# mainboard.net
KiCad netlist of a schematic drawn in EAGLE
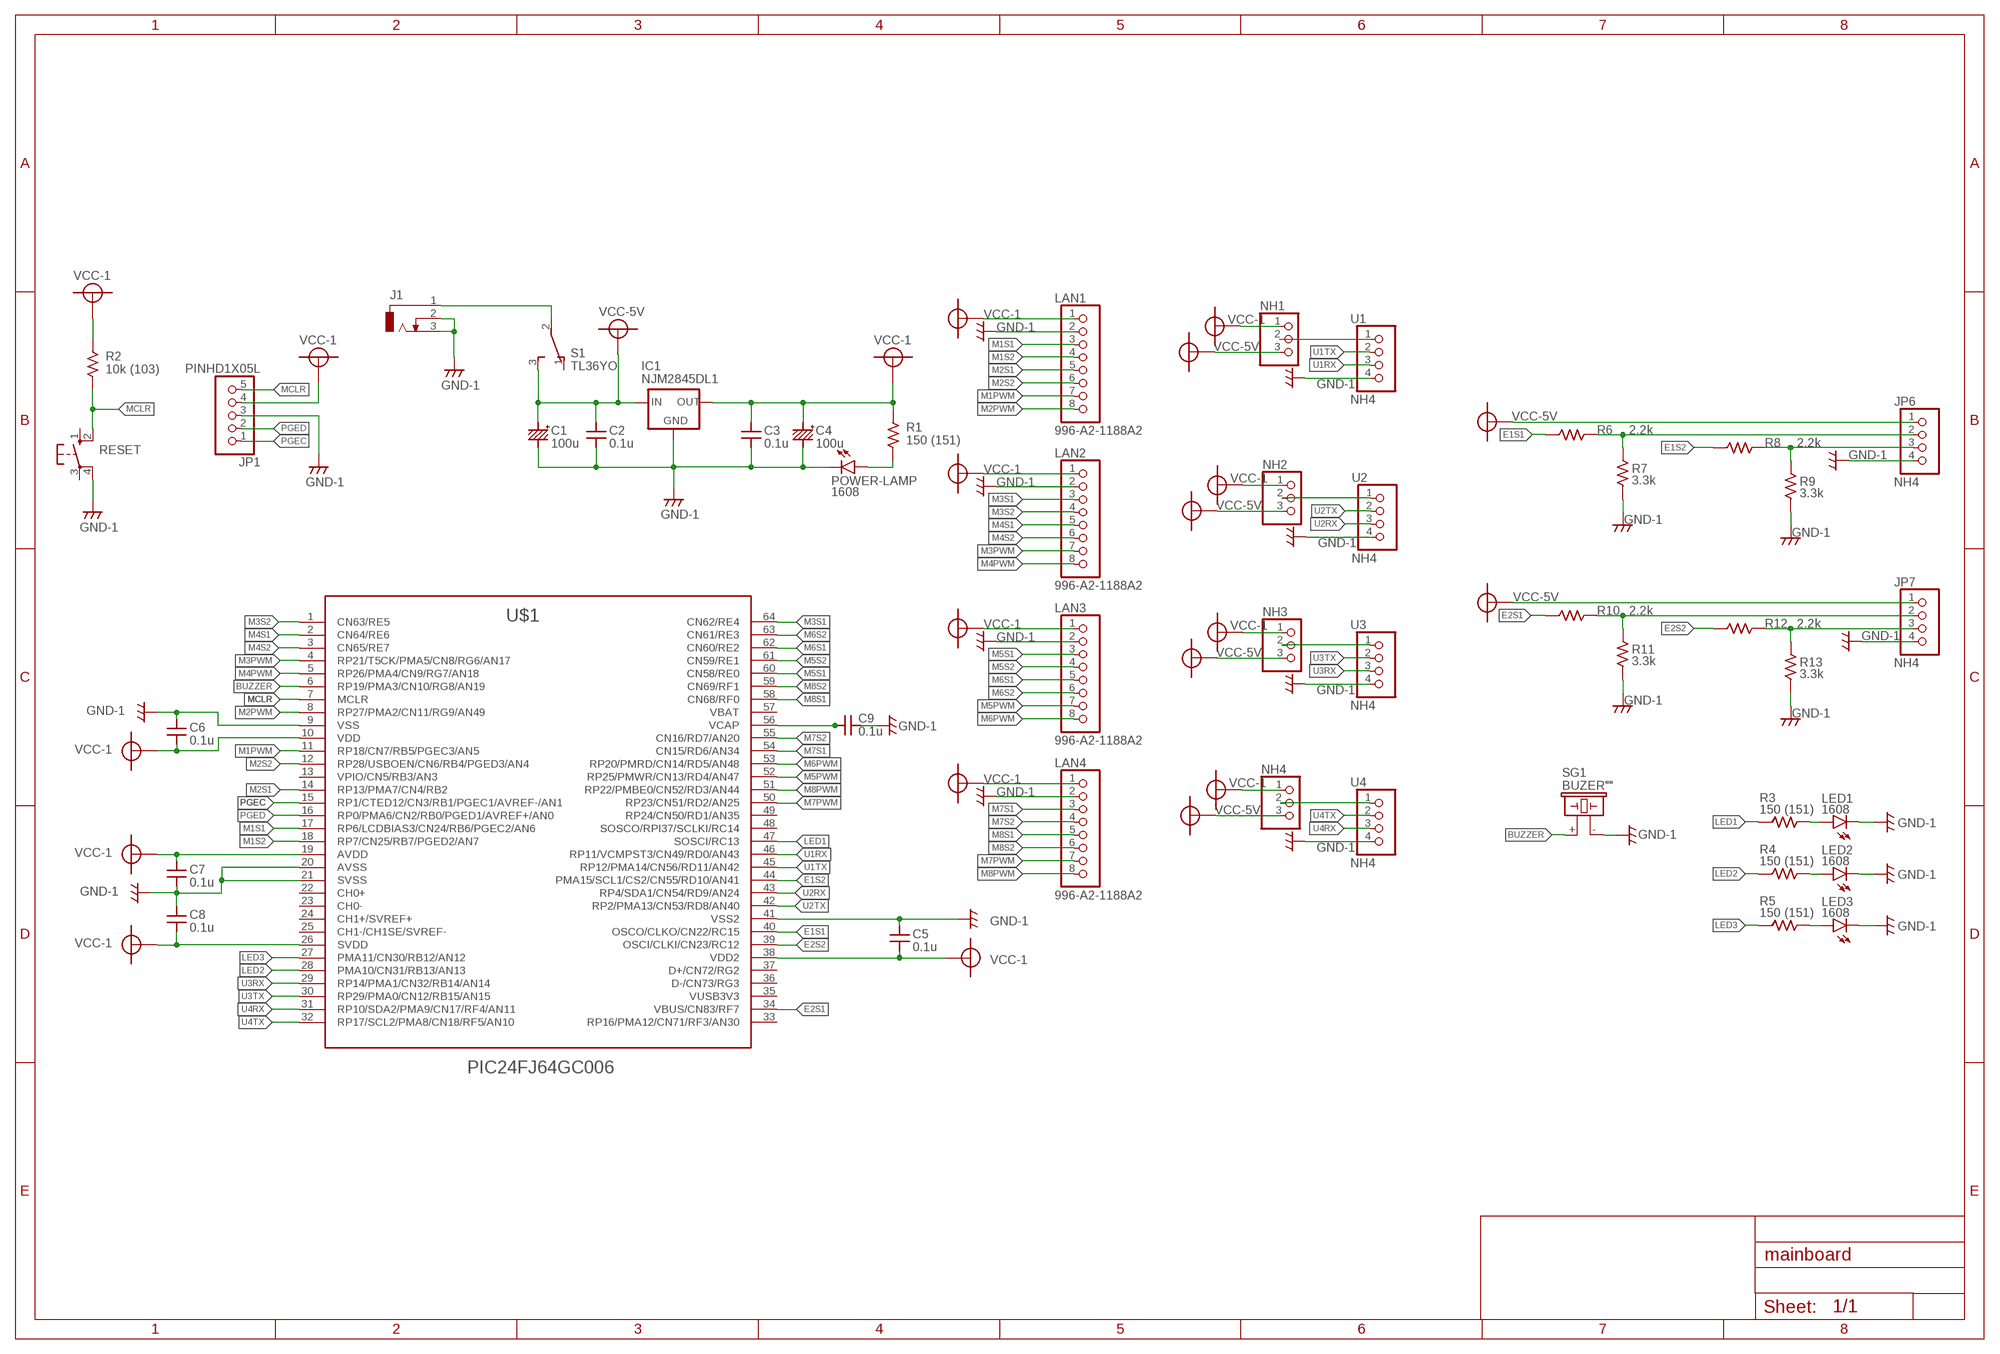
[diagram p0: schematic, sheet 1]

(export (version "E")
  (design (tool "Eeschema 10.0.6"))
  (components
    (comp (ref "C1")
      (value "100u")
      (footprint "eagle-import:CC_3")
      (libsource (lib "eagle-import") (part "C+25V100"))
    )
    (comp (ref "C2")
      (value "0.1u")
      (footprint "eagle-import:C1608")
      (libsource (lib "eagle-import") (part "CC1068"))
    )
    (comp (ref "C3")
      (value "0.1u")
      (footprint "eagle-import:C1608")
      (libsource (lib "eagle-import") (part "CC1068"))
    )
    (comp (ref "C4")
      (value "100u")
      (footprint "eagle-import:CC_3")
      (libsource (lib "eagle-import") (part "C+25V100"))
    )
    (comp (ref "C5")
      (value "0.1u")
      (footprint "eagle-import:C1608")
      (libsource (lib "eagle-import") (part "CC1068"))
    )
    (comp (ref "C6")
      (value "0.1u")
      (footprint "eagle-import:C1608")
      (libsource (lib "eagle-import") (part "CC1068"))
    )
    (comp (ref "C7")
      (value "0.1u")
      (footprint "eagle-import:C1608")
      (libsource (lib "eagle-import") (part "CC1068"))
    )
    (comp (ref "C8")
      (value "0.1u")
      (footprint "eagle-import:C1608")
      (libsource (lib "eagle-import") (part "CC1068"))
    )
    (comp (ref "C9")
      (value "0.1u")
      (footprint "eagle-import:C1608")
      (libsource (lib "eagle-import") (part "CC1068"))
    )
    (comp (ref "IC1")
      (value "NJM2845DL1")
      (footprint "eagle-import:TO252")
      (libsource (lib "eagle-import") (part "NJM2845DL1"))
    )
    (comp (ref "J1")
      (value "DCJ0303")
      (footprint "eagle-import:DCJ0303")
      (libsource (lib "eagle-import") (part "DCJ0303"))
    )
    (comp (ref "JP1")
      (value "PINHD1X05L")
      (footprint "eagle-import:1X05L")
      (libsource (lib "eagle-import") (part "PINHD1X05L"))
    )
    (comp (ref "JP6")
      (value "NH4")
      (footprint "eagle-import:NH4")
      (libsource (lib "eagle-import") (part "NH4"))
    )
    (comp (ref "JP7")
      (value "NH4")
      (footprint "eagle-import:NH4")
      (libsource (lib "eagle-import") (part "NH4"))
    )
    (comp (ref "LAN1")
      (value "996-A2-1188A2")
      (footprint "eagle-import:996-A2-1188A2")
      (libsource (lib "eagle-import") (part "996-A2-1188A2"))
    )
    (comp (ref "LAN2")
      (value "996-A2-1188A2")
      (footprint "eagle-import:996-A2-1188A2")
      (libsource (lib "eagle-import") (part "996-A2-1188A2"))
    )
    (comp (ref "LAN3")
      (value "996-A2-1188A2")
      (footprint "eagle-import:996-A2-1188A2")
      (libsource (lib "eagle-import") (part "996-A2-1188A2"))
    )
    (comp (ref "LAN4")
      (value "996-A2-1188A2")
      (footprint "eagle-import:996-A2-1188A2")
      (libsource (lib "eagle-import") (part "996-A2-1188A2"))
    )
    (comp (ref "LED1")
      (value "1608")
      (footprint "eagle-import:CHIP-LED0603")
      (libsource (lib "eagle-import") (part "LEDCHIP-LED0603"))
    )
    (comp (ref "LED2")
      (value "1608")
      (footprint "eagle-import:CHIP-LED0603")
      (libsource (lib "eagle-import") (part "LEDCHIP-LED0603"))
    )
    (comp (ref "LED3")
      (value "1608")
      (footprint "eagle-import:CHIP-LED0603")
      (libsource (lib "eagle-import") (part "LEDCHIP-LED0603"))
    )
    (comp (ref "NH1")
      (value "PINHD-1X3")
      (footprint "eagle-import:1X03")
      (libsource (lib "eagle-import") (part "PINHD-1X3"))
    )
    (comp (ref "NH2")
      (value "PINHD-1X3")
      (footprint "eagle-import:1X03")
      (libsource (lib "eagle-import") (part "PINHD-1X3"))
    )
    (comp (ref "NH3")
      (value "PINHD-1X3")
      (footprint "eagle-import:1X03")
      (libsource (lib "eagle-import") (part "PINHD-1X3"))
    )
    (comp (ref "NH4")
      (value "PINHD-1X3")
      (footprint "eagle-import:1X03")
      (libsource (lib "eagle-import") (part "PINHD-1X3"))
    )
    (comp (ref "POWER-LAMP")
      (value "1608")
      (footprint "eagle-import:CHIP-LED0603")
      (libsource (lib "eagle-import") (part "LEDCHIP-LED0603"))
    )
    (comp (ref "R1")
      (value "150 (151)")
      (footprint "eagle-import:C1608")
      (libsource (lib "eagle-import") (part "R1/10W"))
    )
    (comp (ref "R2")
      (value "10k (103)")
      (footprint "eagle-import:C1608")
      (libsource (lib "eagle-import") (part "R1/10W"))
    )
    (comp (ref "R3")
      (value "150 (151)")
      (footprint "eagle-import:C1608")
      (libsource (lib "eagle-import") (part "R1/10W"))
    )
    (comp (ref "R4")
      (value "150 (151)")
      (footprint "eagle-import:C1608")
      (libsource (lib "eagle-import") (part "R1/10W"))
    )
    (comp (ref "R5")
      (value "150 (151)")
      (footprint "eagle-import:C1608")
      (libsource (lib "eagle-import") (part "R1/10W"))
    )
    (comp (ref "R6")
      (value "2.2k")
      (footprint "eagle-import:C1608")
      (libsource (lib "eagle-import") (part "R1/10W"))
    )
    (comp (ref "R7")
      (value "3.3k")
      (footprint "eagle-import:C1608")
      (libsource (lib "eagle-import") (part "R1/10W"))
    )
    (comp (ref "R8")
      (value "2.2k")
      (footprint "eagle-import:C1608")
      (libsource (lib "eagle-import") (part "R1/10W"))
    )
    (comp (ref "R9")
      (value "3.3k")
      (footprint "eagle-import:C1608")
      (libsource (lib "eagle-import") (part "R1/10W"))
    )
    (comp (ref "R10")
      (value "2.2k")
      (footprint "eagle-import:C1608")
      (libsource (lib "eagle-import") (part "R1/10W"))
    )
    (comp (ref "R11")
      (value "3.3k")
      (footprint "eagle-import:C1608")
      (libsource (lib "eagle-import") (part "R1/10W"))
    )
    (comp (ref "R12")
      (value "2.2k")
      (footprint "eagle-import:C1608")
      (libsource (lib "eagle-import") (part "R1/10W"))
    )
    (comp (ref "R13")
      (value "3.3k")
      (footprint "eagle-import:C1608")
      (libsource (lib "eagle-import") (part "R1/10W"))
    )
    (comp (ref "RESET")
      (value "10-XX")
      (footprint "eagle-import:B3F-10XX")
      (fields (field (name "MPN") "B3F-1000"))
      (libsource (lib "eagle-import") (part "10-XX"))
    )
    (comp (ref "S1")
      (value "TL36YO")
      (footprint "eagle-import:TL3XYO")
      (libsource (lib "eagle-import") (part "TL36YO"))
    )
    (comp (ref "SG1")
      (value "BUZER\"\"")
      (footprint "eagle-import:F_CM12P")
      (libsource (lib "eagle-import") (part "BUZER{dblquote}{dblquote}"))
    )
    (comp (ref "U$1")
      (value "PIC24FJ64GC006")
      (footprint "eagle-import:TQFP64-10X10")
      (libsource (lib "eagle-import") (part "PIC24FJ64GC006"))
    )
    (comp (ref "U1")
      (value "NH4")
      (footprint "eagle-import:NH4")
      (libsource (lib "eagle-import") (part "NH4"))
    )
    (comp (ref "U2")
      (value "NH4")
      (footprint "eagle-import:NH4")
      (libsource (lib "eagle-import") (part "NH4"))
    )
    (comp (ref "U3")
      (value "NH4")
      (footprint "eagle-import:NH4")
      (libsource (lib "eagle-import") (part "NH4"))
    )
    (comp (ref "U4")
      (value "NH4")
      (footprint "eagle-import:NH4")
      (libsource (lib "eagle-import") (part "NH4"))
    )
  )
  (nets
    (net (code "1") (name "BUZZER") (class "Default")
      (node (ref "SG1") (pin "+") (pinfunction "1_+") (pintype "passive"))
      (node (ref "U$1") (pin "6") (pinfunction "RP19/PMA3/CN10/RG8/AN19_6") (pintype "bidirectional"))
    )
    (net (code "2") (name "E1S1") (class "Default")
      (node (ref "R6") (pin "2") (pinfunction "P$2_2") (pintype "passive"))
      (node (ref "U$1") (pin "40") (pinfunction "OSCO/CLKO/CN22/RC15_40") (pintype "bidirectional"))
    )
    (net (code "3") (name "E1S2") (class "Default")
      (node (ref "R8") (pin "2") (pinfunction "P$2_2") (pintype "passive"))
      (node (ref "U$1") (pin "44") (pinfunction "PMA15/SCL1/CS2/CN55/RD10/AN41_44") (pintype "bidirectional"))
    )
    (net (code "4") (name "E2S1") (class "Default")
      (node (ref "R10") (pin "2") (pinfunction "P$2_2") (pintype "passive"))
      (node (ref "U$1") (pin "34") (pinfunction "VBUS/CN83/RF7_34") (pintype "bidirectional"))
    )
    (net (code "5") (name "E2S2") (class "Default")
      (node (ref "R12") (pin "2") (pinfunction "P$2_2") (pintype "passive"))
      (node (ref "U$1") (pin "39") (pinfunction "OSCI/CLKI/CN23/RC12_39") (pintype "bidirectional"))
    )
    (net (code "6") (name "GND-1") (class "Default")
      (node (ref "C1") (pin "-") (pinfunction "P$2-_-") (pintype "passive"))
      (node (ref "C2") (pin "2") (pinfunction "P$2_2") (pintype "passive"))
      (node (ref "C3") (pin "2") (pinfunction "P$2_2") (pintype "passive"))
      (node (ref "C4") (pin "-") (pinfunction "P$2-_-") (pintype "passive"))
      (node (ref "C5") (pin "1") (pinfunction "P$1_1") (pintype "passive"))
      (node (ref "C6") (pin "1") (pinfunction "P$1_1") (pintype "passive"))
      (node (ref "C7") (pin "2") (pinfunction "P$2_2") (pintype "passive"))
      (node (ref "C8") (pin "1") (pinfunction "P$1_1") (pintype "passive"))
      (node (ref "C9") (pin "2") (pinfunction "P$2_2") (pintype "passive"))
      (node (ref "IC1") (pin "2") (pinfunction "GND_2") (pintype "input"))
      (node (ref "J1") (pin "2") (pinfunction "2_2") (pintype "passive"))
      (node (ref "J1") (pin "3") (pinfunction "3_3") (pintype "passive"))
      (node (ref "JP1") (pin "3") (pinfunction "P$3_3") (pintype "bidirectional"))
      (node (ref "JP6") (pin "4") (pinfunction "P$4_4") (pintype "bidirectional"))
      (node (ref "JP7") (pin "4") (pinfunction "P$4_4") (pintype "bidirectional"))
      (node (ref "LAN1") (pin "2") (pinfunction "P$2_2") (pintype "bidirectional"))
      (node (ref "LAN2") (pin "2") (pinfunction "P$2_2") (pintype "bidirectional"))
      (node (ref "LAN3") (pin "2") (pinfunction "P$2_2") (pintype "bidirectional"))
      (node (ref "LAN4") (pin "2") (pinfunction "P$2_2") (pintype "bidirectional"))
      (node (ref "LED1") (pin "C") (pinfunction "C_C") (pintype "passive"))
      (node (ref "LED2") (pin "C") (pinfunction "C_C") (pintype "passive"))
      (node (ref "LED3") (pin "C") (pinfunction "C_C") (pintype "passive"))
      (node (ref "POWER-LAMP") (pin "C") (pinfunction "C_C") (pintype "passive"))
      (node (ref "R11") (pin "2") (pinfunction "P$2_2") (pintype "passive"))
      (node (ref "R13") (pin "2") (pinfunction "P$2_2") (pintype "passive"))
      (node (ref "R7") (pin "2") (pinfunction "P$2_2") (pintype "passive"))
      (node (ref "R9") (pin "2") (pinfunction "P$2_2") (pintype "passive"))
      (node (ref "RESET") (pin "4") (pinfunction "P1_4") (pintype "passive"))
      (node (ref "SG1") (pin "-") (pinfunction "2_-") (pintype "passive"))
      (node (ref "U$1") (pin "20") (pinfunction "AVSS_20") (pintype "bidirectional"))
      (node (ref "U$1") (pin "21") (pinfunction "SVSS_21") (pintype "bidirectional"))
      (node (ref "U$1") (pin "41") (pinfunction "VSS2_41") (pintype "bidirectional"))
      (node (ref "U$1") (pin "9") (pinfunction "VSS_9") (pintype "bidirectional"))
      (node (ref "U1") (pin "4") (pinfunction "P$4_4") (pintype "bidirectional"))
      (node (ref "U2") (pin "4") (pinfunction "P$4_4") (pintype "bidirectional"))
      (node (ref "U3") (pin "4") (pinfunction "P$4_4") (pintype "bidirectional"))
      (node (ref "U4") (pin "4") (pinfunction "P$4_4") (pintype "bidirectional"))
    )
    (net (code "7") (name "LED1") (class "Default")
      (node (ref "R3") (pin "2") (pinfunction "P$2_2") (pintype "passive"))
      (node (ref "U$1") (pin "47") (pinfunction "SOSCI/RC13_47") (pintype "bidirectional"))
    )
    (net (code "8") (name "LED2") (class "Default")
      (node (ref "R4") (pin "2") (pinfunction "P$2_2") (pintype "passive"))
      (node (ref "U$1") (pin "28") (pinfunction "PMA10/CN31/RB13/AN13_28") (pintype "bidirectional"))
    )
    (net (code "9") (name "LED3") (class "Default")
      (node (ref "R5") (pin "2") (pinfunction "P$2_2") (pintype "passive"))
      (node (ref "U$1") (pin "27") (pinfunction "PMA11/CN30/RB12/AN12_27") (pintype "bidirectional"))
    )
    (net (code "10") (name "M1PWM") (class "Default")
      (node (ref "LAN1") (pin "7") (pinfunction "P$7_7") (pintype "bidirectional"))
      (node (ref "U$1") (pin "11") (pinfunction "RP18/CN7/RB5/PGEC3/AN5_11") (pintype "bidirectional"))
    )
    (net (code "11") (name "M1S1") (class "Default")
      (node (ref "LAN1") (pin "3") (pinfunction "P$3_3") (pintype "bidirectional"))
      (node (ref "U$1") (pin "17") (pinfunction "RP6/LCDBIAS3/CN24/RB6/PGEC2/AN6_17") (pintype "bidirectional"))
    )
    (net (code "12") (name "M1S2") (class "Default")
      (node (ref "LAN1") (pin "4") (pinfunction "P$4_4") (pintype "bidirectional"))
      (node (ref "U$1") (pin "18") (pinfunction "RP7/CN25/RB7/PGED2/AN7_18") (pintype "bidirectional"))
    )
    (net (code "13") (name "M2PWM") (class "Default")
      (node (ref "LAN1") (pin "8") (pinfunction "P$8_8") (pintype "bidirectional"))
      (node (ref "U$1") (pin "8") (pinfunction "RP27/PMA2/CN11/RG9/AN49_8") (pintype "bidirectional"))
    )
    (net (code "14") (name "M2S1") (class "Default")
      (node (ref "LAN1") (pin "5") (pinfunction "P$5_5") (pintype "bidirectional"))
      (node (ref "U$1") (pin "14") (pinfunction "RP13/PMA7/CN4/RB2_14") (pintype "bidirectional"))
    )
    (net (code "15") (name "M2S2") (class "Default")
      (node (ref "LAN1") (pin "6") (pinfunction "P$6_6") (pintype "bidirectional"))
      (node (ref "U$1") (pin "12") (pinfunction "RP28/USBOEN/CN6/RB4/PGED3/AN4_12") (pintype "bidirectional"))
    )
    (net (code "16") (name "M3PWM") (class "Default")
      (node (ref "LAN2") (pin "7") (pinfunction "P$7_7") (pintype "bidirectional"))
      (node (ref "U$1") (pin "4") (pinfunction "RP21/T5CK/PMA5/CN8/RG6/AN17_4") (pintype "bidirectional"))
    )
    (net (code "17") (name "M3S1") (class "Default")
      (node (ref "LAN2") (pin "3") (pinfunction "P$3_3") (pintype "bidirectional"))
      (node (ref "U$1") (pin "64") (pinfunction "CN62/RE4_64") (pintype "bidirectional"))
    )
    (net (code "18") (name "M3S2") (class "Default")
      (node (ref "LAN2") (pin "4") (pinfunction "P$4_4") (pintype "bidirectional"))
      (node (ref "U$1") (pin "1") (pinfunction "CN63/RE5_1") (pintype "bidirectional"))
    )
    (net (code "19") (name "M4PWM") (class "Default")
      (node (ref "LAN2") (pin "8") (pinfunction "P$8_8") (pintype "bidirectional"))
      (node (ref "U$1") (pin "5") (pinfunction "RP26/PMA4/CN9/RG7/AN18_5") (pintype "bidirectional"))
    )
    (net (code "20") (name "M4S1") (class "Default")
      (node (ref "LAN2") (pin "5") (pinfunction "P$5_5") (pintype "bidirectional"))
      (node (ref "U$1") (pin "2") (pinfunction "CN64/RE6_2") (pintype "bidirectional"))
    )
    (net (code "21") (name "M4S2") (class "Default")
      (node (ref "LAN2") (pin "6") (pinfunction "P$6_6") (pintype "bidirectional"))
      (node (ref "U$1") (pin "3") (pinfunction "CN65/RE7_3") (pintype "bidirectional"))
    )
    (net (code "22") (name "M5PWM") (class "Default")
      (node (ref "LAN3") (pin "7") (pinfunction "P$7_7") (pintype "bidirectional"))
      (node (ref "U$1") (pin "52") (pinfunction "RP25/PMWR/CN13/RD4/AN47_52") (pintype "bidirectional"))
    )
    (net (code "23") (name "M5S1") (class "Default")
      (node (ref "LAN3") (pin "3") (pinfunction "P$3_3") (pintype "bidirectional"))
      (node (ref "U$1") (pin "60") (pinfunction "CN58/RE0_60") (pintype "bidirectional"))
    )
    (net (code "24") (name "M5S2") (class "Default")
      (node (ref "LAN3") (pin "4") (pinfunction "P$4_4") (pintype "bidirectional"))
      (node (ref "U$1") (pin "61") (pinfunction "CN59/RE1_61") (pintype "bidirectional"))
    )
    (net (code "25") (name "M6PWM") (class "Default")
      (node (ref "LAN3") (pin "8") (pinfunction "P$8_8") (pintype "bidirectional"))
      (node (ref "U$1") (pin "53") (pinfunction "RP20/PMRD/CN14/RD5/AN48_53") (pintype "bidirectional"))
    )
    (net (code "26") (name "M6S1") (class "Default")
      (node (ref "LAN3") (pin "5") (pinfunction "P$5_5") (pintype "bidirectional"))
      (node (ref "U$1") (pin "62") (pinfunction "CN60/RE2_62") (pintype "bidirectional"))
    )
    (net (code "27") (name "M6S2") (class "Default")
      (node (ref "LAN3") (pin "6") (pinfunction "P$6_6") (pintype "bidirectional"))
      (node (ref "U$1") (pin "63") (pinfunction "CN61/RE3_63") (pintype "bidirectional"))
    )
    (net (code "28") (name "M7PWM") (class "Default")
      (node (ref "LAN4") (pin "7") (pinfunction "P$7_7") (pintype "bidirectional"))
      (node (ref "U$1") (pin "50") (pinfunction "RP23/CN51/RD2/AN25_50") (pintype "bidirectional"))
    )
    (net (code "29") (name "M7S1") (class "Default")
      (node (ref "LAN4") (pin "3") (pinfunction "P$3_3") (pintype "bidirectional"))
      (node (ref "U$1") (pin "54") (pinfunction "CN15/RD6/AN34_54") (pintype "bidirectional"))
    )
    (net (code "30") (name "M7S2") (class "Default")
      (node (ref "LAN4") (pin "4") (pinfunction "P$4_4") (pintype "bidirectional"))
      (node (ref "U$1") (pin "55") (pinfunction "CN16/RD7/AN20_55") (pintype "bidirectional"))
    )
    (net (code "31") (name "M8PWM") (class "Default")
      (node (ref "LAN4") (pin "8") (pinfunction "P$8_8") (pintype "bidirectional"))
      (node (ref "U$1") (pin "51") (pinfunction "RP22/PMBE0/CN52/RD3/AN44_51") (pintype "bidirectional"))
    )
    (net (code "32") (name "M8S1") (class "Default")
      (node (ref "LAN4") (pin "5") (pinfunction "P$5_5") (pintype "bidirectional"))
      (node (ref "U$1") (pin "58") (pinfunction "CN68/RF0_58") (pintype "bidirectional"))
    )
    (net (code "33") (name "M8S2") (class "Default")
      (node (ref "LAN4") (pin "6") (pinfunction "P$6_6") (pintype "bidirectional"))
      (node (ref "U$1") (pin "59") (pinfunction "CN69/RF1_59") (pintype "bidirectional"))
    )
    (net (code "34") (name "MCLR") (class "Default")
      (node (ref "JP1") (pin "5") (pinfunction "P$5_5") (pintype "bidirectional"))
      (node (ref "R2") (pin "1") (pinfunction "P$1_1") (pintype "passive"))
      (node (ref "RESET") (pin "2") (pinfunction "S1_2") (pintype "passive"))
      (node (ref "U$1") (pin "7") (pinfunction "MCLR_7") (pintype "bidirectional"))
    )
    (net (code "35") (name "Net-(C9-P$1)") (class "Default")
      (node (ref "C9") (pin "1") (pinfunction "P$1_1") (pintype "passive"))
      (node (ref "U$1") (pin "56") (pinfunction "VCAP_56") (pintype "bidirectional"))
    )
    (net (code "36") (name "Net-(JP6-P$2)") (class "Default")
      (node (ref "JP6") (pin "2") (pinfunction "P$2_2") (pintype "bidirectional"))
      (node (ref "R6") (pin "1") (pinfunction "P$1_1") (pintype "passive"))
      (node (ref "R7") (pin "1") (pinfunction "P$1_1") (pintype "passive"))
    )
    (net (code "37") (name "Net-(JP6-P$3)") (class "Default")
      (node (ref "JP6") (pin "3") (pinfunction "P$3_3") (pintype "bidirectional"))
      (node (ref "R8") (pin "1") (pinfunction "P$1_1") (pintype "passive"))
      (node (ref "R9") (pin "1") (pinfunction "P$1_1") (pintype "passive"))
    )
    (net (code "38") (name "Net-(JP7-P$2)") (class "Default")
      (node (ref "JP7") (pin "2") (pinfunction "P$2_2") (pintype "bidirectional"))
      (node (ref "R10") (pin "1") (pinfunction "P$1_1") (pintype "passive"))
      (node (ref "R11") (pin "1") (pinfunction "P$1_1") (pintype "passive"))
    )
    (net (code "39") (name "Net-(JP7-P$3)") (class "Default")
      (node (ref "JP7") (pin "3") (pinfunction "P$3_3") (pintype "bidirectional"))
      (node (ref "R12") (pin "1") (pinfunction "P$1_1") (pintype "passive"))
      (node (ref "R13") (pin "1") (pinfunction "P$1_1") (pintype "passive"))
    )
    (net (code "40") (name "Net-(R1-P$1)") (class "Default")
      (node (ref "POWER-LAMP") (pin "A") (pinfunction "A_A") (pintype "passive"))
      (node (ref "R1") (pin "1") (pinfunction "P$1_1") (pintype "passive"))
    )
    (net (code "41") (name "Net-(R3-P$1)") (class "Default")
      (node (ref "LED1") (pin "A") (pinfunction "A_A") (pintype "passive"))
      (node (ref "R3") (pin "1") (pinfunction "P$1_1") (pintype "passive"))
    )
    (net (code "42") (name "Net-(R4-P$1)") (class "Default")
      (node (ref "LED2") (pin "A") (pinfunction "A_A") (pintype "passive"))
      (node (ref "R4") (pin "1") (pinfunction "P$1_1") (pintype "passive"))
    )
    (net (code "43") (name "Net-(R5-P$1)") (class "Default")
      (node (ref "LED3") (pin "A") (pinfunction "A_A") (pintype "passive"))
      (node (ref "R5") (pin "1") (pinfunction "P$1_1") (pintype "passive"))
    )
    (net (code "44") (name "Net-(S1-P)") (class "Default")
      (node (ref "J1") (pin "1") (pinfunction "1_1") (pintype "passive"))
      (node (ref "S1") (pin "2") (pinfunction "P_2") (pintype "passive"))
    )
    (net (code "45") (name "Net-(U1-P$1)") (class "Default")
      (node (ref "NH1") (pin "2") (pinfunction "2_2") (pintype "passive"))
      (node (ref "U1") (pin "1") (pinfunction "P$1_1") (pintype "bidirectional"))
    )
    (net (code "46") (name "Net-(U2-P$1)") (class "Default")
      (node (ref "NH2") (pin "2") (pinfunction "2_2") (pintype "passive"))
      (node (ref "U2") (pin "1") (pinfunction "P$1_1") (pintype "bidirectional"))
    )
    (net (code "47") (name "Net-(U3-P$1)") (class "Default")
      (node (ref "NH3") (pin "2") (pinfunction "2_2") (pintype "passive"))
      (node (ref "U3") (pin "1") (pinfunction "P$1_1") (pintype "bidirectional"))
    )
    (net (code "48") (name "Net-(U4-P$1)") (class "Default")
      (node (ref "NH4") (pin "2") (pinfunction "2_2") (pintype "passive"))
      (node (ref "U4") (pin "1") (pinfunction "P$1_1") (pintype "bidirectional"))
    )
    (net (code "49") (name "PGEC") (class "Default")
      (node (ref "JP1") (pin "1") (pinfunction "P$1_1") (pintype "bidirectional"))
      (node (ref "U$1") (pin "15") (pinfunction "RP1/CTED12/CN3/RB1/PGEC1/AVREF-/AN1_15") (pintype "bidirectional"))
    )
    (net (code "50") (name "PGED") (class "Default")
      (node (ref "JP1") (pin "2") (pinfunction "P$2_2") (pintype "bidirectional"))
      (node (ref "U$1") (pin "16") (pinfunction "RP0/PMA6/CN2/RB0/PGED1/AVREF+/AN0_16") (pintype "bidirectional"))
    )
    (net (code "51") (name "U1RX") (class "Default")
      (node (ref "U$1") (pin "46") (pinfunction "RP11/VCMPST3/CN49/RD0/AN43_46") (pintype "bidirectional"))
      (node (ref "U1") (pin "3") (pinfunction "P$3_3") (pintype "bidirectional"))
    )
    (net (code "52") (name "U1TX") (class "Default")
      (node (ref "U$1") (pin "45") (pinfunction "RP12/PMA14/CN56/RD11/AN42_45") (pintype "bidirectional"))
      (node (ref "U1") (pin "2") (pinfunction "P$2_2") (pintype "bidirectional"))
    )
    (net (code "53") (name "U2RX") (class "Default")
      (node (ref "U$1") (pin "43") (pinfunction "RP4/SDA1/CN54/RD9/AN24_43") (pintype "bidirectional"))
      (node (ref "U2") (pin "3") (pinfunction "P$3_3") (pintype "bidirectional"))
    )
    (net (code "54") (name "U2TX") (class "Default")
      (node (ref "U$1") (pin "42") (pinfunction "RP2/PMA13/CN53/RD8/AN40_42") (pintype "bidirectional"))
      (node (ref "U2") (pin "2") (pinfunction "P$2_2") (pintype "bidirectional"))
    )
    (net (code "55") (name "U3RX") (class "Default")
      (node (ref "U$1") (pin "29") (pinfunction "RP14/PMA1/CN32/RB14/AN14_29") (pintype "bidirectional"))
      (node (ref "U3") (pin "3") (pinfunction "P$3_3") (pintype "bidirectional"))
    )
    (net (code "56") (name "U3TX") (class "Default")
      (node (ref "U$1") (pin "30") (pinfunction "RP29/PMA0/CN12/RB15/AN15_30") (pintype "bidirectional"))
      (node (ref "U3") (pin "2") (pinfunction "P$2_2") (pintype "bidirectional"))
    )
    (net (code "57") (name "U4RX") (class "Default")
      (node (ref "U$1") (pin "31") (pinfunction "RP10/SDA2/PMA9/CN17/RF4/AN11_31") (pintype "bidirectional"))
      (node (ref "U4") (pin "3") (pinfunction "P$3_3") (pintype "bidirectional"))
    )
    (net (code "58") (name "U4TX") (class "Default")
      (node (ref "U$1") (pin "32") (pinfunction "RP17/SCL2/PMA8/CN18/RF5/AN10_32") (pintype "bidirectional"))
      (node (ref "U4") (pin "2") (pinfunction "P$2_2") (pintype "bidirectional"))
    )
    (net (code "59") (name "VCC-1") (class "Default")
      (node (ref "C3") (pin "1") (pinfunction "P$1_1") (pintype "passive"))
      (node (ref "C4") (pin "+") (pinfunction "P$1+_+") (pintype "passive"))
      (node (ref "C5") (pin "2") (pinfunction "P$2_2") (pintype "passive"))
      (node (ref "C6") (pin "2") (pinfunction "P$2_2") (pintype "passive"))
      (node (ref "C7") (pin "1") (pinfunction "P$1_1") (pintype "passive"))
      (node (ref "C8") (pin "2") (pinfunction "P$2_2") (pintype "passive"))
      (node (ref "IC1") (pin "3") (pinfunction "OUT_3") (pintype "passive"))
      (node (ref "JP1") (pin "4") (pinfunction "P$4_4") (pintype "bidirectional"))
      (node (ref "LAN1") (pin "1") (pinfunction "P$1_1") (pintype "bidirectional"))
      (node (ref "LAN2") (pin "1") (pinfunction "P$1_1") (pintype "bidirectional"))
      (node (ref "LAN3") (pin "1") (pinfunction "P$1_1") (pintype "bidirectional"))
      (node (ref "LAN4") (pin "1") (pinfunction "P$1_1") (pintype "bidirectional"))
      (node (ref "NH1") (pin "1") (pinfunction "1_1") (pintype "passive"))
      (node (ref "NH2") (pin "1") (pinfunction "1_1") (pintype "passive"))
      (node (ref "NH3") (pin "1") (pinfunction "1_1") (pintype "passive"))
      (node (ref "NH4") (pin "1") (pinfunction "1_1") (pintype "passive"))
      (node (ref "R1") (pin "2") (pinfunction "P$2_2") (pintype "passive"))
      (node (ref "R2") (pin "2") (pinfunction "P$2_2") (pintype "passive"))
      (node (ref "U$1") (pin "10") (pinfunction "VDD_10") (pintype "bidirectional"))
      (node (ref "U$1") (pin "19") (pinfunction "AVDD_19") (pintype "bidirectional"))
      (node (ref "U$1") (pin "26") (pinfunction "SVDD_26") (pintype "bidirectional"))
      (node (ref "U$1") (pin "38") (pinfunction "VDD2_38") (pintype "bidirectional"))
    )
    (net (code "60") (name "VCC-5V") (class "Default")
      (node (ref "C1") (pin "+") (pinfunction "P$1+_+") (pintype "passive"))
      (node (ref "C2") (pin "1") (pinfunction "P$1_1") (pintype "passive"))
      (node (ref "IC1") (pin "1") (pinfunction "IN_1") (pintype "input"))
      (node (ref "JP6") (pin "1") (pinfunction "P$1_1") (pintype "bidirectional"))
      (node (ref "JP7") (pin "1") (pinfunction "P$1_1") (pintype "bidirectional"))
      (node (ref "NH1") (pin "3") (pinfunction "3_3") (pintype "passive"))
      (node (ref "NH2") (pin "3") (pinfunction "3_3") (pintype "passive"))
      (node (ref "NH3") (pin "3") (pinfunction "3_3") (pintype "passive"))
      (node (ref "NH4") (pin "3") (pinfunction "3_3") (pintype "passive"))
      (node (ref "S1") (pin "3") (pinfunction "S_3") (pintype "passive"))
    )
    (net (code "61") (name "unconnected-(RESET-P-Pad3)") (class "Default")
      (node (ref "RESET") (pin "3") (pinfunction "P_3") (pintype "passive"))
    )
    (net (code "62") (name "unconnected-(RESET-S-Pad1)") (class "Default")
      (node (ref "RESET") (pin "1") (pinfunction "S_1") (pintype "passive"))
    )
    (net (code "63") (name "unconnected-(S1-O-Pad1)") (class "Default")
      (node (ref "S1") (pin "1") (pinfunction "O_1") (pintype "passive"))
    )
    (net (code "64") (name "unconnected-(U$1-CH0+-Pad22)") (class "Default")
      (node (ref "U$1") (pin "22") (pinfunction "CH0+_22") (pintype "bidirectional"))
    )
    (net (code "65") (name "unconnected-(U$1-CH0--Pad23)") (class "Default")
      (node (ref "U$1") (pin "23") (pinfunction "CH0-_23") (pintype "bidirectional"))
    )
    (net (code "66") (name "unconnected-(U$1-CH1+{slash}SVREF+-Pad24)") (class "Default")
      (node (ref "U$1") (pin "24") (pinfunction "CH1+/SVREF+_24") (pintype "bidirectional"))
    )
    (net (code "67") (name "unconnected-(U$1-CH1-{slash}CH1SE{slash}SVREF--Pad25)") (class "Default")
      (node (ref "U$1") (pin "25") (pinfunction "CH1-/CH1SE/SVREF-_25") (pintype "bidirectional"))
    )
    (net (code "68") (name "unconnected-(U$1-D+{slash}CN72{slash}RG2-Pad37)") (class "Default")
      (node (ref "U$1") (pin "37") (pinfunction "D+/CN72/RG2_37") (pintype "bidirectional"))
    )
    (net (code "69") (name "unconnected-(U$1-D-{slash}CN73{slash}RG3-Pad36)") (class "Default")
      (node (ref "U$1") (pin "36") (pinfunction "D-/CN73/RG3_36") (pintype "bidirectional"))
    )
    (net (code "70") (name "unconnected-(U$1-RP16{slash}PMA12{slash}CN71{slash}RF3{slash}AN30-Pad33)") (class "Default")
      (node (ref "U$1") (pin "33") (pinfunction "RP16/PMA12/CN71/RF3/AN30_33") (pintype "bidirectional"))
    )
    (net (code "71") (name "unconnected-(U$1-RP24{slash}CN50{slash}RD1{slash}AN35-Pad49)") (class "Default")
      (node (ref "U$1") (pin "49") (pinfunction "RP24/CN50/RD1/AN35_49") (pintype "bidirectional"))
    )
    (net (code "72") (name "unconnected-(U$1-SOSCO{slash}RPI37{slash}SCLKI{slash}RC14-Pad48)") (class "Default")
      (node (ref "U$1") (pin "48") (pinfunction "SOSCO/RPI37/SCLKI/RC14_48") (pintype "bidirectional"))
    )
    (net (code "73") (name "unconnected-(U$1-VBAT-Pad57)") (class "Default")
      (node (ref "U$1") (pin "57") (pinfunction "VBAT_57") (pintype "bidirectional"))
    )
    (net (code "74") (name "unconnected-(U$1-VPIO{slash}CN5{slash}RB3{slash}AN3-Pad13)") (class "Default")
      (node (ref "U$1") (pin "13") (pinfunction "VPIO/CN5/RB3/AN3_13") (pintype "bidirectional"))
    )
    (net (code "75") (name "unconnected-(U$1-VUSB3V3-Pad35)") (class "Default")
      (node (ref "U$1") (pin "35") (pinfunction "VUSB3V3_35") (pintype "bidirectional"))
    )
  )
)
